# USB3_0.net
KiCad netlist of a schematic drawn in Altium Designer
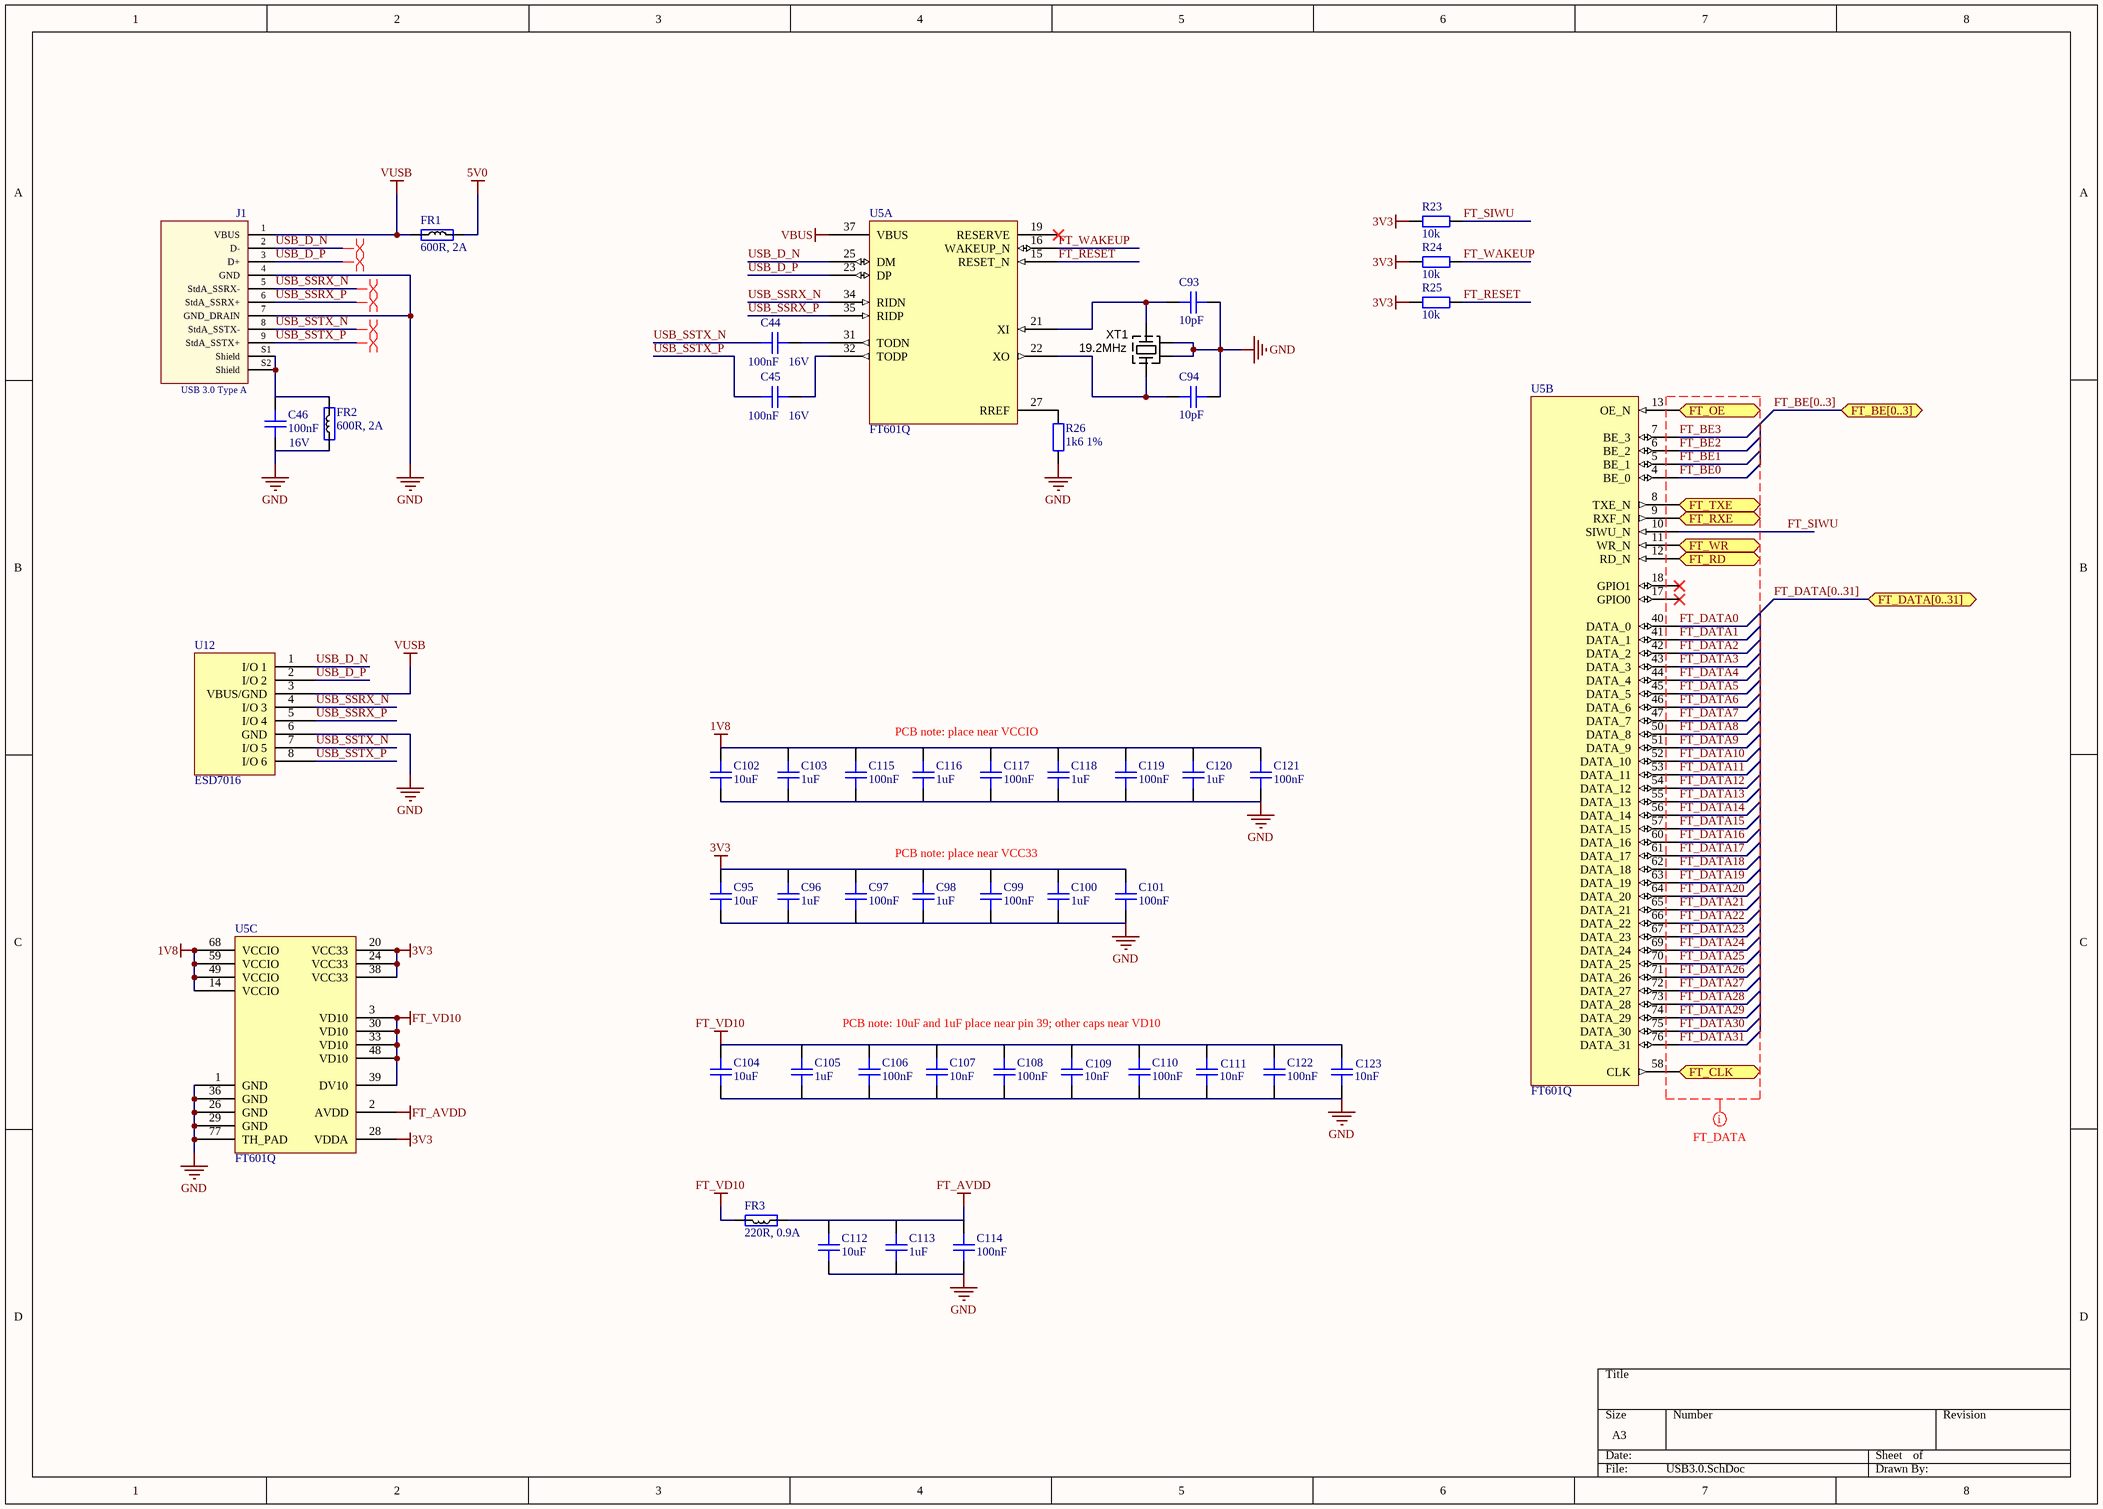
[diagram p0: USB3.0.SchDoc]

(export (version "E")
  (design (tool "Eeschema 10.0.6"))
  (components
    (comp (ref "C44")
      (value "100nF")
      (footprint "CAP0402")
      (fields (field (name "VOLTAGE RATING") "16V"))
      (libsource (lib "WaveRadio") (part "Cap_0402"))
    )
    (comp (ref "C45")
      (value "100nF")
      (footprint "CAP0402")
      (fields (field (name "VOLTAGE RATING") "16V"))
      (libsource (lib "WaveRadio") (part "Cap_0402"))
    )
    (comp (ref "C46")
      (value "100nF")
      (footprint "CAP0402")
      (fields (field (name "VOLTAGE RATING") "16V"))
      (libsource (lib "WaveRadio") (part "Cap_0402"))
    )
    (comp (ref "C93") (value "10pF") (footprint "CAP0402") (libsource (lib "WaveRadio") (part "Cap_0402")))
    (comp (ref "C94") (value "10pF") (footprint "CAP0402") (libsource (lib "WaveRadio") (part "Cap_0402")))
    (comp (ref "C95") (value "10uF") (footprint "CAP0402") (libsource (lib "WaveRadio") (part "Cap_0402")))
    (comp (ref "C96") (value "1uF") (footprint "CAP0402") (libsource (lib "WaveRadio") (part "Cap_0402")))
    (comp (ref "C97") (value "100nF") (footprint "CAP0402") (libsource (lib "WaveRadio") (part "Cap_0402")))
    (comp (ref "C98") (value "1uF") (footprint "CAP0402") (libsource (lib "WaveRadio") (part "Cap_0402")))
    (comp (ref "C99") (value "100nF") (footprint "CAP0402") (libsource (lib "WaveRadio") (part "Cap_0402")))
    (comp (ref "C100") (value "1uF") (footprint "CAP0402") (libsource (lib "WaveRadio") (part "Cap_0402")))
    (comp (ref "C101") (value "100nF") (footprint "CAP0402") (libsource (lib "WaveRadio") (part "Cap_0402")))
    (comp (ref "C102") (value "10uF") (footprint "CAP0402") (libsource (lib "WaveRadio") (part "Cap_0402")))
    (comp (ref "C103") (value "1uF") (footprint "CAP0402") (libsource (lib "WaveRadio") (part "Cap_0402")))
    (comp (ref "C104") (value "10uF") (footprint "CAP0402") (libsource (lib "WaveRadio") (part "Cap_0402")))
    (comp (ref "C105") (value "1uF") (footprint "CAP0402") (libsource (lib "WaveRadio") (part "Cap_0402")))
    (comp (ref "C106") (value "100nF") (footprint "CAP0402") (libsource (lib "WaveRadio") (part "Cap_0402")))
    (comp (ref "C107") (value "10nF") (footprint "CAP0402") (libsource (lib "WaveRadio") (part "Cap_0402")))
    (comp (ref "C108") (value "100nF") (footprint "CAP0402") (libsource (lib "WaveRadio") (part "Cap_0402")))
    (comp (ref "C109") (value "10nF") (footprint "CAP0402") (libsource (lib "WaveRadio") (part "Cap_0402")))
    (comp (ref "C110") (value "100nF") (footprint "CAP0402") (libsource (lib "WaveRadio") (part "Cap_0402")))
    (comp (ref "C111") (value "10nF") (footprint "CAP0402") (libsource (lib "WaveRadio") (part "Cap_0402")))
    (comp (ref "C112") (value "10uF") (footprint "CAP0402") (libsource (lib "WaveRadio") (part "Cap_0402")))
    (comp (ref "C113") (value "1uF") (footprint "CAP0402") (libsource (lib "WaveRadio") (part "Cap_0402")))
    (comp (ref "C114") (value "100nF") (footprint "CAP0402") (libsource (lib "WaveRadio") (part "Cap_0402")))
    (comp (ref "C115") (value "100nF") (footprint "CAP0402") (libsource (lib "WaveRadio") (part "Cap_0402")))
    (comp (ref "C116") (value "1uF") (footprint "CAP0402") (libsource (lib "WaveRadio") (part "Cap_0402")))
    (comp (ref "C117") (value "100nF") (footprint "CAP0402") (libsource (lib "WaveRadio") (part "Cap_0402")))
    (comp (ref "C118") (value "1uF") (footprint "CAP0402") (libsource (lib "WaveRadio") (part "Cap_0402")))
    (comp (ref "C119") (value "100nF") (footprint "CAP0402") (libsource (lib "WaveRadio") (part "Cap_0402")))
    (comp (ref "C120") (value "1uF") (footprint "CAP0402") (libsource (lib "WaveRadio") (part "Cap_0402")))
    (comp (ref "C121") (value "100nF") (footprint "CAP0402") (libsource (lib "WaveRadio") (part "Cap_0402")))
    (comp (ref "C122") (value "100nF") (footprint "CAP0402") (libsource (lib "WaveRadio") (part "Cap_0402")))
    (comp (ref "C123") (value "10nF") (footprint "CAP0402") (libsource (lib "WaveRadio") (part "Cap_0402")))
    (comp (ref "FR1") (value "600R, 2A") (footprint "RES0402") (libsource (lib "WaveRadio") (part "Ferrite")))
    (comp (ref "FR2") (value "600R, 2A") (footprint "RES0402") (libsource (lib "WaveRadio") (part "Ferrite")))
    (comp (ref "FR3")
      (value "220R, 0.9A")
      (footprint "RES0402")
      (libsource (lib "WaveRadio") (part "Ferrite"))
    )
    (comp (ref "J1")
      (value "USB 3.0 Type A")
      (footprint "692122030100")
      (description "USB 3.0 Type A Horizontal SMT WR-COM")
      (fields (field (name "PART NUMBER") "692122030100") (field (name "PUBLISHER") "Wurth Elektronik"))
      (libsource (lib "Altium_WR-COM_USB-Connectors (rev18a)") (part "692122030100"))
    )
    (comp (ref "R23") (value "10k") (footprint "RES0402") (libsource (lib "WaveRadio") (part "Res_0402")))
    (comp (ref "R24") (value "10k") (footprint "RES0402") (libsource (lib "WaveRadio") (part "Res_0402")))
    (comp (ref "R25") (value "10k") (footprint "RES0402") (libsource (lib "WaveRadio") (part "Res_0402")))
    (comp (ref "R26") (value "1k6 1%") (footprint "RES0402") (libsource (lib "WaveRadio") (part "Res_0402")))
    (comp (ref "U5")
      (value "FT601Q")
      (footprint "FT601Q")
      (fields (field (name "MANUFACTURER") "FTDI, Future Technology Devices International Ltd"))
      (libsource (lib "WaveRadio") (part "FT601Q"))
    )
    (comp (ref "U12")
      (value "ESD7016")
      (footprint "ESD7016")
      (fields (field (name "MANUFACTURER") "ON Semiconductor"))
      (libsource (lib "WaveRadio") (part "ESD7016"))
    )
    (comp (ref "XT1")
      (value "19.2MHz")
      (footprint "CRYSTAL_4-LCC")
      (description "Oscillator Crystal 27.12 MHz 10ppm")
      (libsource (lib "WaveRadio") (part "CRYSTAL_19M2"))
    )
  )
  (nets
    (net (code "1") (name "/FT_BE0") (class "Default")
      (node (ref "U5") (pin "4") (pinfunction "BE_0_4") (pintype "bidirectional"))
    )
    (net (code "2") (name "/FT_BE1") (class "Default")
      (node (ref "U5") (pin "5") (pinfunction "BE_1_5") (pintype "bidirectional"))
    )
    (net (code "3") (name "/FT_BE2") (class "Default")
      (node (ref "U5") (pin "6") (pinfunction "BE_2_6") (pintype "bidirectional"))
    )
    (net (code "4") (name "/FT_BE3") (class "Default")
      (node (ref "U5") (pin "7") (pinfunction "BE_3_7") (pintype "bidirectional"))
    )
    (net (code "6") (name "/FT_CLK") (class "Default")
      (node (ref "U5") (pin "58") (pinfunction "CLK_58") (pintype "output"))
    )
    (net (code "7") (name "/FT_DATA0") (class "Default")
      (node (ref "U5") (pin "40") (pinfunction "DATA_0_40") (pintype "bidirectional"))
    )
    (net (code "8") (name "/FT_DATA1") (class "Default")
      (node (ref "U5") (pin "41") (pinfunction "DATA_1_41") (pintype "bidirectional"))
    )
    (net (code "9") (name "/FT_DATA2") (class "Default")
      (node (ref "U5") (pin "42") (pinfunction "DATA_2_42") (pintype "bidirectional"))
    )
    (net (code "10") (name "/FT_DATA3") (class "Default")
      (node (ref "U5") (pin "43") (pinfunction "DATA_3_43") (pintype "bidirectional"))
    )
    (net (code "11") (name "/FT_DATA4") (class "Default")
      (node (ref "U5") (pin "44") (pinfunction "DATA_4_44") (pintype "bidirectional"))
    )
    (net (code "12") (name "/FT_DATA5") (class "Default")
      (node (ref "U5") (pin "45") (pinfunction "DATA_5_45") (pintype "bidirectional"))
    )
    (net (code "13") (name "/FT_DATA6") (class "Default")
      (node (ref "U5") (pin "46") (pinfunction "DATA_6_46") (pintype "bidirectional"))
    )
    (net (code "14") (name "/FT_DATA7") (class "Default")
      (node (ref "U5") (pin "47") (pinfunction "DATA_7_47") (pintype "bidirectional"))
    )
    (net (code "15") (name "/FT_DATA8") (class "Default")
      (node (ref "U5") (pin "50") (pinfunction "DATA_8_50") (pintype "bidirectional"))
    )
    (net (code "16") (name "/FT_DATA9") (class "Default")
      (node (ref "U5") (pin "51") (pinfunction "DATA_9_51") (pintype "bidirectional"))
    )
    (net (code "17") (name "/FT_DATA10") (class "Default")
      (node (ref "U5") (pin "52") (pinfunction "DATA_10_52") (pintype "bidirectional"))
    )
    (net (code "18") (name "/FT_DATA11") (class "Default")
      (node (ref "U5") (pin "53") (pinfunction "DATA_11_53") (pintype "bidirectional"))
    )
    (net (code "19") (name "/FT_DATA12") (class "Default")
      (node (ref "U5") (pin "54") (pinfunction "DATA_12_54") (pintype "bidirectional"))
    )
    (net (code "20") (name "/FT_DATA13") (class "Default")
      (node (ref "U5") (pin "55") (pinfunction "DATA_13_55") (pintype "bidirectional"))
    )
    (net (code "21") (name "/FT_DATA14") (class "Default")
      (node (ref "U5") (pin "56") (pinfunction "DATA_14_56") (pintype "bidirectional"))
    )
    (net (code "22") (name "/FT_DATA15") (class "Default")
      (node (ref "U5") (pin "57") (pinfunction "DATA_15_57") (pintype "bidirectional"))
    )
    (net (code "23") (name "/FT_DATA16") (class "Default")
      (node (ref "U5") (pin "60") (pinfunction "DATA_16_60") (pintype "bidirectional"))
    )
    (net (code "24") (name "/FT_DATA17") (class "Default")
      (node (ref "U5") (pin "61") (pinfunction "DATA_17_61") (pintype "bidirectional"))
    )
    (net (code "25") (name "/FT_DATA18") (class "Default")
      (node (ref "U5") (pin "62") (pinfunction "DATA_18_62") (pintype "bidirectional"))
    )
    (net (code "26") (name "/FT_DATA19") (class "Default")
      (node (ref "U5") (pin "63") (pinfunction "DATA_19_63") (pintype "bidirectional"))
    )
    (net (code "27") (name "/FT_DATA20") (class "Default")
      (node (ref "U5") (pin "64") (pinfunction "DATA_20_64") (pintype "bidirectional"))
    )
    (net (code "28") (name "/FT_DATA21") (class "Default")
      (node (ref "U5") (pin "65") (pinfunction "DATA_21_65") (pintype "bidirectional"))
    )
    (net (code "29") (name "/FT_DATA22") (class "Default")
      (node (ref "U5") (pin "66") (pinfunction "DATA_22_66") (pintype "bidirectional"))
    )
    (net (code "30") (name "/FT_DATA23") (class "Default")
      (node (ref "U5") (pin "67") (pinfunction "DATA_23_67") (pintype "bidirectional"))
    )
    (net (code "31") (name "/FT_DATA24") (class "Default")
      (node (ref "U5") (pin "69") (pinfunction "DATA_24_69") (pintype "bidirectional"))
    )
    (net (code "32") (name "/FT_DATA25") (class "Default")
      (node (ref "U5") (pin "70") (pinfunction "DATA_25_70") (pintype "bidirectional"))
    )
    (net (code "33") (name "/FT_DATA26") (class "Default")
      (node (ref "U5") (pin "71") (pinfunction "DATA_26_71") (pintype "bidirectional"))
    )
    (net (code "34") (name "/FT_DATA27") (class "Default")
      (node (ref "U5") (pin "72") (pinfunction "DATA_27_72") (pintype "bidirectional"))
    )
    (net (code "35") (name "/FT_DATA28") (class "Default")
      (node (ref "U5") (pin "73") (pinfunction "DATA_28_73") (pintype "bidirectional"))
    )
    (net (code "36") (name "/FT_DATA29") (class "Default")
      (node (ref "U5") (pin "74") (pinfunction "DATA_29_74") (pintype "bidirectional"))
    )
    (net (code "37") (name "/FT_DATA30") (class "Default")
      (node (ref "U5") (pin "75") (pinfunction "DATA_30_75") (pintype "bidirectional"))
    )
    (net (code "38") (name "/FT_DATA31") (class "Default")
      (node (ref "U5") (pin "76") (pinfunction "DATA_31_76") (pintype "bidirectional"))
    )
    (net (code "40") (name "/FT_OE") (class "Default")
      (node (ref "U5") (pin "13") (pinfunction "OE_N_13") (pintype "input"))
    )
    (net (code "41") (name "/FT_RD") (class "Default")
      (node (ref "U5") (pin "12") (pinfunction "RD_N_12") (pintype "input"))
    )
    (net (code "42") (name "/FT_RESET") (class "Default")
      (node (ref "U5") (pin "15") (pinfunction "RESET_N_15") (pintype "input"))
    )
    (net (code "43") (name "/FT_RXE") (class "Default")
      (node (ref "U5") (pin "9") (pinfunction "RXF_N_9") (pintype "output"))
    )
    (net (code "44") (name "/FT_SIWU") (class "Default")
      (node (ref "U5") (pin "10") (pinfunction "SIWU_N_10") (pintype "input"))
    )
    (net (code "45") (name "/FT_TXE") (class "Default")
      (node (ref "U5") (pin "8") (pinfunction "TXE_N_8") (pintype "output"))
    )
    (net (code "46") (name "/FT_WAKEUP") (class "Default")
      (node (ref "U5") (pin "16") (pinfunction "WAKEUP_N_16") (pintype "bidirectional"))
    )
    (net (code "47") (name "/FT_WR") (class "Default")
      (node (ref "U5") (pin "11") (pinfunction "WR_N_11") (pintype "input"))
    )
    (net (code "48") (name "/USB_D_N") (class "Default")
      (node (ref "J1") (pin "2") (pinfunction "D-_2") (pintype "passive"))
      (node (ref "U12") (pin "1") (pinfunction "I/O_1_1") (pintype "passive"))
      (node (ref "U5") (pin "25") (pinfunction "DM_25") (pintype "bidirectional"))
    )
    (net (code "49") (name "/USB_D_P") (class "Default")
      (node (ref "J1") (pin "3") (pinfunction "D+_3") (pintype "passive"))
      (node (ref "U12") (pin "2") (pinfunction "I/O_2_2") (pintype "passive"))
      (node (ref "U5") (pin "23") (pinfunction "DP_23") (pintype "bidirectional"))
    )
    (net (code "50") (name "/USB_SSRX_N") (class "Default")
      (node (ref "J1") (pin "5") (pinfunction "StdA_SSRX-_5") (pintype "passive"))
      (node (ref "U12") (pin "4") (pinfunction "I/O_3_4") (pintype "passive"))
      (node (ref "U5") (pin "34") (pinfunction "RIDN_34") (pintype "input"))
    )
    (net (code "51") (name "/USB_SSRX_P") (class "Default")
      (node (ref "J1") (pin "6") (pinfunction "StdA_SSRX+_6") (pintype "passive"))
      (node (ref "U12") (pin "5") (pinfunction "I/O_4_5") (pintype "passive"))
      (node (ref "U5") (pin "35") (pinfunction "RIDP_35") (pintype "input"))
    )
    (net (code "52") (name "/USB_SSTX_N") (class "Default")
      (node (ref "C44") (pin "2") (pinfunction "2_2") (pintype "passive"))
      (node (ref "J1") (pin "8") (pinfunction "StdA_SSTX-_8") (pintype "passive"))
      (node (ref "U12") (pin "7") (pinfunction "I/O_5_7") (pintype "passive"))
    )
    (net (code "53") (name "/USB_SSTX_P") (class "Default")
      (node (ref "C45") (pin "2") (pinfunction "2_2") (pintype "passive"))
      (node (ref "J1") (pin "9") (pinfunction "StdA_SSTX+_9") (pintype "passive"))
      (node (ref "U12") (pin "8") (pinfunction "I/O_6_8") (pintype "passive"))
    )
    (net (code "54") (name "1V8") (class "Default")
      (node (ref "U5") (pin "14") (pinfunction "VCCIO_14") (pintype "passive"))
      (node (ref "U5") (pin "49") (pinfunction "VCCIO_49") (pintype "passive"))
      (node (ref "U5") (pin "59") (pinfunction "VCCIO_59") (pintype "passive"))
      (node (ref "U5") (pin "68") (pinfunction "VCCIO_68") (pintype "passive"))
    )
    (net (code "55") (name "3V3") (class "Default")
      (node (ref "U5") (pin "20") (pinfunction "VCC33_20") (pintype "passive"))
      (node (ref "U5") (pin "24") (pinfunction "VCC33_24") (pintype "passive"))
      (node (ref "U5") (pin "28") (pinfunction "VDDA_28") (pintype "passive"))
      (node (ref "U5") (pin "38") (pinfunction "VCC33_38") (pintype "passive"))
    )
    (net (code "57") (name "FT_AVDD") (class "Default")
      (node (ref "U5") (pin "2") (pinfunction "AVDD_2") (pintype "passive"))
    )
    (net (code "58") (name "FT_VD10") (class "Default")
      (node (ref "U5") (pin "3") (pinfunction "VD10_3") (pintype "passive"))
      (node (ref "U5") (pin "30") (pinfunction "VD10_30") (pintype "passive"))
      (node (ref "U5") (pin "33") (pinfunction "VD10_33") (pintype "passive"))
      (node (ref "U5") (pin "39") (pinfunction "DV10_39") (pintype "passive"))
      (node (ref "U5") (pin "48") (pinfunction "VD10_48") (pintype "passive"))
    )
    (net (code "59") (name "GND") (class "Default")
      (node (ref "J1") (pin "4") (pinfunction "GND_4") (pintype "passive"))
      (node (ref "J1") (pin "7") (pinfunction "GND_DRAIN_7") (pintype "passive"))
      (node (ref "U12") (pin "6") (pinfunction "GND_6") (pintype "passive"))
      (node (ref "U5") (pin "1") (pinfunction "GND_1") (pintype "passive"))
      (node (ref "U5") (pin "26") (pinfunction "GND_26") (pintype "passive"))
      (node (ref "U5") (pin "29") (pinfunction "GND_29") (pintype "passive"))
      (node (ref "U5") (pin "36") (pinfunction "GND_36") (pintype "passive"))
      (node (ref "U5") (pin "77") (pinfunction "TH_PAD_77") (pintype "passive"))
    )
    (net (code "60") (name "Net-(J1-Shield-PadS1)") (class "Default")
      (node (ref "J1") (pin "S1") (pinfunction "Shield_S1") (pintype "passive"))
      (node (ref "J1") (pin "S2") (pinfunction "Shield_S2") (pintype "passive"))
    )
    (net (code "61") (name "VBUS") (class "Default")
      (node (ref "U5") (pin "37") (pinfunction "VBUS_37") (pintype "passive"))
    )
    (net (code "62") (name "VUSB") (class "Default")
      (node (ref "J1") (pin "1") (pinfunction "VBUS_1") (pintype "passive"))
      (node (ref "U12") (pin "3") (pinfunction "VBUS/GND_3") (pintype "passive"))
    )
    (net (code "63") (name "unconnected-(C44-Pad1)") (class "Default")
      (node (ref "C44") (pin "1") (pinfunction "1_1") (pintype "passive"))
    )
    (net (code "64") (name "unconnected-(C45-Pad1)") (class "Default")
      (node (ref "C45") (pin "1") (pinfunction "1_1") (pintype "passive"))
    )
    (net (code "65") (name "unconnected-(C46-Pad1)") (class "Default")
      (node (ref "C46") (pin "1") (pinfunction "1_1") (pintype "passive"))
    )
    (net (code "66") (name "unconnected-(C46-Pad2)") (class "Default")
      (node (ref "C46") (pin "2") (pinfunction "2_2") (pintype "passive"))
    )
    (net (code "67") (name "unconnected-(C93-Pad1)") (class "Default")
      (node (ref "C93") (pin "1") (pinfunction "1_1") (pintype "passive"))
    )
    (net (code "68") (name "unconnected-(C93-Pad2)") (class "Default")
      (node (ref "C93") (pin "2") (pinfunction "2_2") (pintype "passive"))
    )
    (net (code "69") (name "unconnected-(C94-Pad1)") (class "Default")
      (node (ref "C94") (pin "1") (pinfunction "1_1") (pintype "passive"))
    )
    (net (code "70") (name "unconnected-(C94-Pad2)") (class "Default")
      (node (ref "C94") (pin "2") (pinfunction "2_2") (pintype "passive"))
    )
    (net (code "71") (name "unconnected-(C95-Pad1)") (class "Default")
      (node (ref "C95") (pin "1") (pinfunction "1_1") (pintype "passive"))
    )
    (net (code "72") (name "unconnected-(C95-Pad2)") (class "Default")
      (node (ref "C95") (pin "2") (pinfunction "2_2") (pintype "passive"))
    )
    (net (code "73") (name "unconnected-(C96-Pad1)") (class "Default")
      (node (ref "C96") (pin "1") (pinfunction "1_1") (pintype "passive"))
    )
    (net (code "74") (name "unconnected-(C96-Pad2)") (class "Default")
      (node (ref "C96") (pin "2") (pinfunction "2_2") (pintype "passive"))
    )
    (net (code "75") (name "unconnected-(C97-Pad1)") (class "Default")
      (node (ref "C97") (pin "1") (pinfunction "1_1") (pintype "passive"))
    )
    (net (code "76") (name "unconnected-(C97-Pad2)") (class "Default")
      (node (ref "C97") (pin "2") (pinfunction "2_2") (pintype "passive"))
    )
    (net (code "77") (name "unconnected-(C98-Pad1)") (class "Default")
      (node (ref "C98") (pin "1") (pinfunction "1_1") (pintype "passive"))
    )
    (net (code "78") (name "unconnected-(C98-Pad2)") (class "Default")
      (node (ref "C98") (pin "2") (pinfunction "2_2") (pintype "passive"))
    )
    (net (code "79") (name "unconnected-(C99-Pad1)") (class "Default")
      (node (ref "C99") (pin "1") (pinfunction "1_1") (pintype "passive"))
    )
    (net (code "80") (name "unconnected-(C99-Pad2)") (class "Default")
      (node (ref "C99") (pin "2") (pinfunction "2_2") (pintype "passive"))
    )
    (net (code "81") (name "unconnected-(C100-Pad1)") (class "Default")
      (node (ref "C100") (pin "1") (pinfunction "1_1") (pintype "passive"))
    )
    (net (code "82") (name "unconnected-(C100-Pad2)") (class "Default")
      (node (ref "C100") (pin "2") (pinfunction "2_2") (pintype "passive"))
    )
    (net (code "83") (name "unconnected-(C101-Pad1)") (class "Default")
      (node (ref "C101") (pin "1") (pinfunction "1_1") (pintype "passive"))
    )
    (net (code "84") (name "unconnected-(C101-Pad2)") (class "Default")
      (node (ref "C101") (pin "2") (pinfunction "2_2") (pintype "passive"))
    )
    (net (code "85") (name "unconnected-(C102-Pad1)") (class "Default")
      (node (ref "C102") (pin "1") (pinfunction "1_1") (pintype "passive"))
    )
    (net (code "86") (name "unconnected-(C102-Pad2)") (class "Default")
      (node (ref "C102") (pin "2") (pinfunction "2_2") (pintype "passive"))
    )
    (net (code "87") (name "unconnected-(C103-Pad1)") (class "Default")
      (node (ref "C103") (pin "1") (pinfunction "1_1") (pintype "passive"))
    )
    (net (code "88") (name "unconnected-(C103-Pad2)") (class "Default")
      (node (ref "C103") (pin "2") (pinfunction "2_2") (pintype "passive"))
    )
    (net (code "89") (name "unconnected-(C104-Pad1)") (class "Default")
      (node (ref "C104") (pin "1") (pinfunction "1_1") (pintype "passive"))
    )
    (net (code "90") (name "unconnected-(C104-Pad2)") (class "Default")
      (node (ref "C104") (pin "2") (pinfunction "2_2") (pintype "passive"))
    )
    (net (code "91") (name "unconnected-(C105-Pad1)") (class "Default")
      (node (ref "C105") (pin "1") (pinfunction "1_1") (pintype "passive"))
    )
    (net (code "92") (name "unconnected-(C105-Pad2)") (class "Default")
      (node (ref "C105") (pin "2") (pinfunction "2_2") (pintype "passive"))
    )
    (net (code "93") (name "unconnected-(C106-Pad1)") (class "Default")
      (node (ref "C106") (pin "1") (pinfunction "1_1") (pintype "passive"))
    )
    (net (code "94") (name "unconnected-(C106-Pad2)") (class "Default")
      (node (ref "C106") (pin "2") (pinfunction "2_2") (pintype "passive"))
    )
    (net (code "95") (name "unconnected-(C107-Pad1)") (class "Default")
      (node (ref "C107") (pin "1") (pinfunction "1_1") (pintype "passive"))
    )
    (net (code "96") (name "unconnected-(C107-Pad2)") (class "Default")
      (node (ref "C107") (pin "2") (pinfunction "2_2") (pintype "passive"))
    )
    (net (code "97") (name "unconnected-(C108-Pad1)") (class "Default")
      (node (ref "C108") (pin "1") (pinfunction "1_1") (pintype "passive"))
    )
    (net (code "98") (name "unconnected-(C108-Pad2)") (class "Default")
      (node (ref "C108") (pin "2") (pinfunction "2_2") (pintype "passive"))
    )
    (net (code "99") (name "unconnected-(C109-Pad1)") (class "Default")
      (node (ref "C109") (pin "1") (pinfunction "1_1") (pintype "passive"))
    )
    (net (code "100") (name "unconnected-(C109-Pad2)") (class "Default")
      (node (ref "C109") (pin "2") (pinfunction "2_2") (pintype "passive"))
    )
    (net (code "101") (name "unconnected-(C110-Pad1)") (class "Default")
      (node (ref "C110") (pin "1") (pinfunction "1_1") (pintype "passive"))
    )
    (net (code "102") (name "unconnected-(C110-Pad2)") (class "Default")
      (node (ref "C110") (pin "2") (pinfunction "2_2") (pintype "passive"))
    )
    (net (code "103") (name "unconnected-(C111-Pad1)") (class "Default")
      (node (ref "C111") (pin "1") (pinfunction "1_1") (pintype "passive"))
    )
    (net (code "104") (name "unconnected-(C111-Pad2)") (class "Default")
      (node (ref "C111") (pin "2") (pinfunction "2_2") (pintype "passive"))
    )
    (net (code "105") (name "unconnected-(C112-Pad1)") (class "Default")
      (node (ref "C112") (pin "1") (pinfunction "1_1") (pintype "passive"))
    )
    (net (code "106") (name "unconnected-(C112-Pad2)") (class "Default")
      (node (ref "C112") (pin "2") (pinfunction "2_2") (pintype "passive"))
    )
    (net (code "107") (name "unconnected-(C113-Pad1)") (class "Default")
      (node (ref "C113") (pin "1") (pinfunction "1_1") (pintype "passive"))
    )
    (net (code "108") (name "unconnected-(C113-Pad2)") (class "Default")
      (node (ref "C113") (pin "2") (pinfunction "2_2") (pintype "passive"))
    )
    (net (code "109") (name "unconnected-(C114-Pad1)") (class "Default")
      (node (ref "C114") (pin "1") (pinfunction "1_1") (pintype "passive"))
    )
    (net (code "110") (name "unconnected-(C114-Pad2)") (class "Default")
      (node (ref "C114") (pin "2") (pinfunction "2_2") (pintype "passive"))
    )
    (net (code "111") (name "unconnected-(C115-Pad1)") (class "Default")
      (node (ref "C115") (pin "1") (pinfunction "1_1") (pintype "passive"))
    )
    (net (code "112") (name "unconnected-(C115-Pad2)") (class "Default")
      (node (ref "C115") (pin "2") (pinfunction "2_2") (pintype "passive"))
    )
    (net (code "113") (name "unconnected-(C116-Pad1)") (class "Default")
      (node (ref "C116") (pin "1") (pinfunction "1_1") (pintype "passive"))
    )
    (net (code "114") (name "unconnected-(C116-Pad2)") (class "Default")
      (node (ref "C116") (pin "2") (pinfunction "2_2") (pintype "passive"))
    )
    (net (code "115") (name "unconnected-(C117-Pad1)") (class "Default")
      (node (ref "C117") (pin "1") (pinfunction "1_1") (pintype "passive"))
    )
    (net (code "116") (name "unconnected-(C117-Pad2)") (class "Default")
      (node (ref "C117") (pin "2") (pinfunction "2_2") (pintype "passive"))
    )
    (net (code "117") (name "unconnected-(C118-Pad1)") (class "Default")
      (node (ref "C118") (pin "1") (pinfunction "1_1") (pintype "passive"))
    )
    (net (code "118") (name "unconnected-(C118-Pad2)") (class "Default")
      (node (ref "C118") (pin "2") (pinfunction "2_2") (pintype "passive"))
    )
    (net (code "119") (name "unconnected-(C119-Pad1)") (class "Default")
      (node (ref "C119") (pin "1") (pinfunction "1_1") (pintype "passive"))
    )
    (net (code "120") (name "unconnected-(C119-Pad2)") (class "Default")
      (node (ref "C119") (pin "2") (pinfunction "2_2") (pintype "passive"))
    )
    (net (code "121") (name "unconnected-(C120-Pad1)") (class "Default")
      (node (ref "C120") (pin "1") (pinfunction "1_1") (pintype "passive"))
    )
    (net (code "122") (name "unconnected-(C120-Pad2)") (class "Default")
      (node (ref "C120") (pin "2") (pinfunction "2_2") (pintype "passive"))
    )
    (net (code "123") (name "unconnected-(C121-Pad1)") (class "Default")
      (node (ref "C121") (pin "1") (pinfunction "1_1") (pintype "passive"))
    )
    (net (code "124") (name "unconnected-(C121-Pad2)") (class "Default")
      (node (ref "C121") (pin "2") (pinfunction "2_2") (pintype "passive"))
    )
    (net (code "125") (name "unconnected-(C122-Pad1)") (class "Default")
      (node (ref "C122") (pin "1") (pinfunction "1_1") (pintype "passive"))
    )
    (net (code "126") (name "unconnected-(C122-Pad2)") (class "Default")
      (node (ref "C122") (pin "2") (pinfunction "2_2") (pintype "passive"))
    )
    (net (code "127") (name "unconnected-(C123-Pad1)") (class "Default")
      (node (ref "C123") (pin "1") (pinfunction "1_1") (pintype "passive"))
    )
    (net (code "128") (name "unconnected-(C123-Pad2)") (class "Default")
      (node (ref "C123") (pin "2") (pinfunction "2_2") (pintype "passive"))
    )
    (net (code "129") (name "unconnected-(FR1-Pad1)") (class "Default")
      (node (ref "FR1") (pin "1") (pinfunction "1_1") (pintype "passive"))
    )
    (net (code "130") (name "unconnected-(FR1-Pad2)") (class "Default")
      (node (ref "FR1") (pin "2") (pinfunction "2_2") (pintype "passive"))
    )
    (net (code "131") (name "unconnected-(FR2-Pad1)") (class "Default")
      (node (ref "FR2") (pin "1") (pinfunction "1_1") (pintype "passive"))
    )
    (net (code "132") (name "unconnected-(FR2-Pad2)") (class "Default")
      (node (ref "FR2") (pin "2") (pinfunction "2_2") (pintype "passive"))
    )
    (net (code "133") (name "unconnected-(FR3-Pad1)") (class "Default")
      (node (ref "FR3") (pin "1") (pinfunction "1_1") (pintype "passive"))
    )
    (net (code "134") (name "unconnected-(FR3-Pad2)") (class "Default")
      (node (ref "FR3") (pin "2") (pinfunction "2_2") (pintype "passive"))
    )
    (net (code "135") (name "unconnected-(R23-Pad1)") (class "Default")
      (node (ref "R23") (pin "1") (pintype "passive"))
    )
    (net (code "136") (name "unconnected-(R23-Pad2)") (class "Default")
      (node (ref "R23") (pin "2") (pintype "passive"))
    )
    (net (code "137") (name "unconnected-(R24-Pad1)") (class "Default")
      (node (ref "R24") (pin "1") (pintype "passive"))
    )
    (net (code "138") (name "unconnected-(R24-Pad2)") (class "Default")
      (node (ref "R24") (pin "2") (pintype "passive"))
    )
    (net (code "139") (name "unconnected-(R25-Pad1)") (class "Default")
      (node (ref "R25") (pin "1") (pintype "passive"))
    )
    (net (code "140") (name "unconnected-(R25-Pad2)") (class "Default")
      (node (ref "R25") (pin "2") (pintype "passive"))
    )
    (net (code "141") (name "unconnected-(R26-Pad1)") (class "Default")
      (node (ref "R26") (pin "1") (pintype "passive"))
    )
    (net (code "142") (name "unconnected-(R26-Pad2)") (class "Default")
      (node (ref "R26") (pin "2") (pintype "passive"))
    )
    (net (code "143") (name "unconnected-(U5A-RESERVE-Pad19)") (class "Default")
      (node (ref "U5") (pin "19") (pinfunction "RESERVE_19") (pintype "passive+no_connect"))
    )
    (net (code "144") (name "unconnected-(U5A-RREF-Pad27)") (class "Default")
      (node (ref "U5") (pin "27") (pinfunction "RREF_27") (pintype "passive"))
    )
    (net (code "145") (name "unconnected-(U5A-TODN-Pad31)") (class "Default")
      (node (ref "U5") (pin "31") (pinfunction "TODN_31") (pintype "output"))
    )
    (net (code "146") (name "unconnected-(U5A-TODP-Pad32)") (class "Default")
      (node (ref "U5") (pin "32") (pinfunction "TODP_32") (pintype "output"))
    )
    (net (code "147") (name "unconnected-(U5A-XI-Pad21)") (class "Default")
      (node (ref "U5") (pin "21") (pinfunction "XI_21") (pintype "input"))
    )
    (net (code "148") (name "unconnected-(U5A-XO-Pad22)") (class "Default")
      (node (ref "U5") (pin "22") (pinfunction "XO_22") (pintype "output"))
    )
    (net (code "149") (name "unconnected-(U5B-GPIO0-Pad17)") (class "Default")
      (node (ref "U5") (pin "17") (pinfunction "GPIO0_17") (pintype "bidirectional+no_connect"))
    )
    (net (code "150") (name "unconnected-(U5B-GPIO1-Pad18)") (class "Default")
      (node (ref "U5") (pin "18") (pinfunction "GPIO1_18") (pintype "bidirectional+no_connect"))
    )
    (net (code "151") (name "unconnected-(XT1-GND-Pad2)") (class "Default")
      (node (ref "XT1") (pin "2") (pinfunction "GND_2") (pintype "passive"))
    )
    (net (code "152") (name "unconnected-(XT1-GND-Pad4)") (class "Default")
      (node (ref "XT1") (pin "4") (pinfunction "GND_4") (pintype "passive"))
    )
    (net (code "153") (name "unconnected-(XT1-X-Pad1)") (class "Default")
      (node (ref "XT1") (pin "1") (pinfunction "X_1") (pintype "passive"))
    )
    (net (code "154") (name "unconnected-(XT1-X-Pad3)") (class "Default")
      (node (ref "XT1") (pin "3") (pinfunction "X_3") (pintype "passive"))
    )
  )
)
